# ESP32_main.net
KiCad netlist of a schematic drawn in Altium Designer
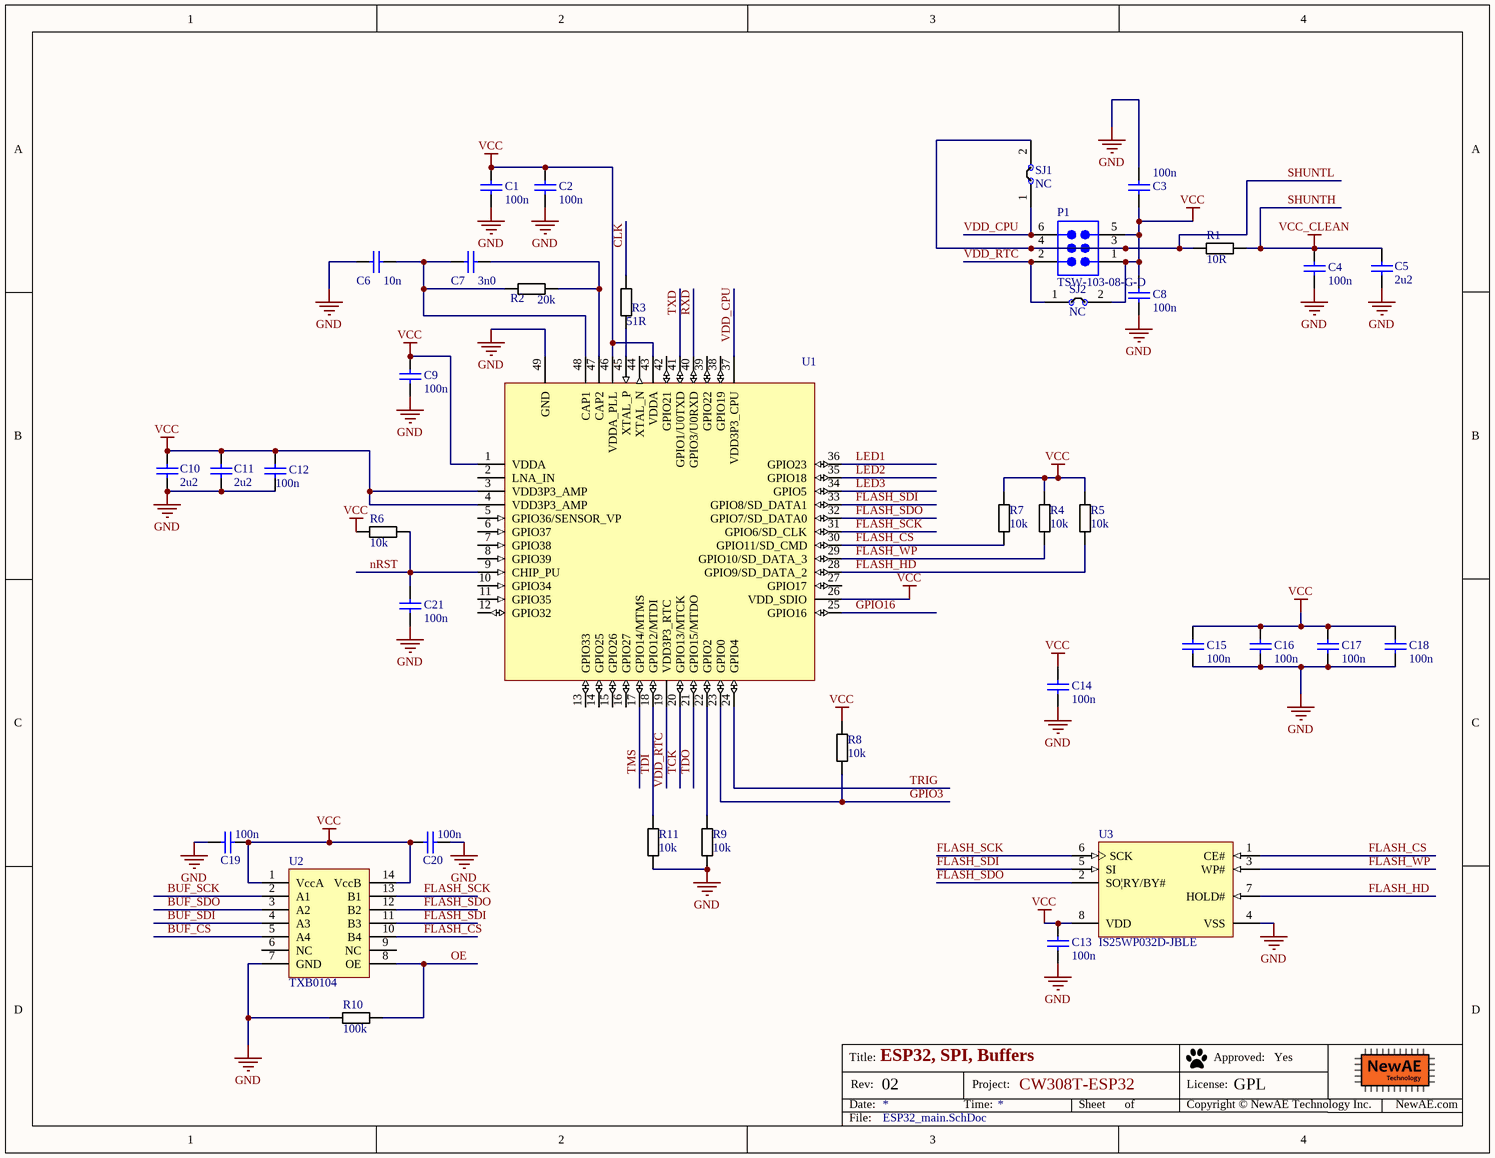
[diagram p0: ESP32_main.SchDoc]

(export (version "E")
  (design (tool "Eeschema 10.0.6"))
  (components
    (comp (ref "C1")
      (value "100n")
      (footprint "CAPC0603_M")
      (description "100n, 0603")
      (fields (field (name "PART NUMBER") "CCHIP-100n-0603"))
      (libsource (lib "NewAE_AltiumLib") (part "CAP"))
    )
    (comp (ref "C2")
      (value "100n")
      (footprint "CAPC0603_M")
      (description "100n, 0603")
      (fields (field (name "PART NUMBER") "CCHIP-100n-0603"))
      (libsource (lib "NewAE_AltiumLib") (part "CAP"))
    )
    (comp (ref "C3")
      (value "100n")
      (footprint "CAPC0603_M")
      (description "100n, 0603")
      (fields (field (name "PART NUMBER") "CCHIP-100n-0603"))
      (libsource (lib "NewAE_AltiumLib") (part "CAP"))
    )
    (comp (ref "C4")
      (value "100n")
      (footprint "CAPC0603_M")
      (description "100n, 0603")
      (fields (field (name "PART NUMBER") "CCHIP-100n-0603"))
      (libsource (lib "NewAE_AltiumLib") (part "CAP"))
    )
    (comp (ref "C5")
      (value "2u2")
      (footprint "CAPC0603_M")
      (description "2u2, 0603")
      (fields (field (name "PART NUMBER") "CCHIP-2u2-0603"))
      (libsource (lib "NewAE_AltiumLib") (part "CAP"))
    )
    (comp (ref "C6")
      (value "10n")
      (footprint "CAPC0603_M")
      (description "10n, 0603")
      (fields (field (name "PART NUMBER") "CCHIP-10n-0603"))
      (libsource (lib "NewAE_AltiumLib") (part "CAP"))
    )
    (comp (ref "C7")
      (value "3n0")
      (footprint "CAPC0603_M")
      (description "3n0, 0603")
      (fields (field (name "PART NUMBER") "CCHIP-3n0-0603"))
      (libsource (lib "NewAE_AltiumLib") (part "CAP"))
    )
    (comp (ref "C8")
      (value "100n")
      (footprint "CAPC0603_M")
      (description "100n, 0603")
      (fields (field (name "PART NUMBER") "CCHIP-100n-0603"))
      (libsource (lib "NewAE_AltiumLib") (part "CAP"))
    )
    (comp (ref "C9")
      (value "100n")
      (footprint "CAPC0603_M")
      (description "100n, 0603")
      (fields (field (name "PART NUMBER") "CCHIP-100n-0603"))
      (libsource (lib "NewAE_AltiumLib") (part "CAP"))
    )
    (comp (ref "C10")
      (value "2u2")
      (footprint "CAPC0603_M")
      (description "2u2, 0603")
      (fields (field (name "PART NUMBER") "CCHIP-2u2-0603"))
      (libsource (lib "NewAE_AltiumLib") (part "CAP"))
    )
    (comp (ref "C11")
      (value "2u2")
      (footprint "CAPC0603_M")
      (description "2u2, 0603")
      (fields (field (name "PART NUMBER") "CCHIP-2u2-0603"))
      (libsource (lib "NewAE_AltiumLib") (part "CAP"))
    )
    (comp (ref "C12")
      (value "100n")
      (footprint "CAPC0603_M")
      (description "100n, 0603")
      (fields (field (name "PART NUMBER") "CCHIP-100n-0603"))
      (libsource (lib "NewAE_AltiumLib") (part "CAP"))
    )
    (comp (ref "C13")
      (value "100n")
      (footprint "CAPC0603_M")
      (description "100n, 0603")
      (fields (field (name "PART NUMBER") "CCHIP-100n-0603"))
      (libsource (lib "NewAE_AltiumLib") (part "CAP"))
    )
    (comp (ref "C14")
      (value "100n")
      (footprint "CAPC0603_M")
      (description "100n, 0603")
      (fields (field (name "PART NUMBER") "CCHIP-100n-0603"))
      (libsource (lib "NewAE_AltiumLib") (part "CAP"))
    )
    (comp (ref "C15")
      (value "100n")
      (footprint "CAPC0603_M")
      (description "100n, 0603")
      (fields (field (name "PART NUMBER") "CCHIP-100n-0603"))
      (libsource (lib "NewAE_AltiumLib") (part "CAP"))
    )
    (comp (ref "C16")
      (value "100n")
      (footprint "CAPC0603_M")
      (description "100n, 0603")
      (fields (field (name "PART NUMBER") "CCHIP-100n-0603"))
      (libsource (lib "NewAE_AltiumLib") (part "CAP"))
    )
    (comp (ref "C17")
      (value "100n")
      (footprint "CAPC0603_M")
      (description "100n, 0603")
      (fields (field (name "PART NUMBER") "CCHIP-100n-0603"))
      (libsource (lib "NewAE_AltiumLib") (part "CAP"))
    )
    (comp (ref "C18")
      (value "100n")
      (footprint "CAPC0603_M")
      (description "100n, 0603")
      (fields (field (name "PART NUMBER") "CCHIP-100n-0603"))
      (libsource (lib "NewAE_AltiumLib") (part "CAP"))
    )
    (comp (ref "C19")
      (value "100n")
      (footprint "CAPC0603_M")
      (description "100n, 0603")
      (fields (field (name "PART NUMBER") "CCHIP-100n-0603"))
      (libsource (lib "NewAE_AltiumLib") (part "CAP"))
    )
    (comp (ref "C20")
      (value "100n")
      (footprint "CAPC0603_M")
      (description "100n, 0603")
      (fields (field (name "PART NUMBER") "CCHIP-100n-0603"))
      (libsource (lib "NewAE_AltiumLib") (part "CAP"))
    )
    (comp (ref "C21")
      (value "100n")
      (footprint "CAPC0603_M")
      (description "100n, 0603")
      (fields (field (name "PART NUMBER") "CCHIP-100n-0603"))
      (libsource (lib "NewAE_AltiumLib") (part "CAP"))
    )
    (comp (ref "P1")
      (value "TSW-103-08-G-D")
      (footprint "SMTC-TSW-103-08-X-D")
      (fields (field (name "MANUFACTURER") "Samtec"))
      (libsource (lib "Altium Content Vault") (part "SMTC-TSW-103-08-X-D"))
    )
    (comp (ref "R1")
      (value "10R")
      (footprint "RESC1608X55N")
      (description "10R res, 0603, 1%, 1/10W")
      (fields (field (name "PART NUMBER") "RCHIP-10R-0603") (field (name "TOLERANCE") "1%"))
      (libsource (lib "NewAE_AltiumLib") (part "RES-EU"))
    )
    (comp (ref "R2")
      (value "20k")
      (footprint "RESC1608X55N")
      (description "20k res, 0603, 1%, 1/10W")
      (fields (field (name "PART NUMBER") "RCHIP-20K-0603") (field (name "TOLERANCE") "1%"))
      (libsource (lib "NewAE_AltiumLib") (part "RES-EU"))
    )
    (comp (ref "R3")
      (value "51R")
      (footprint "RESC1608X55N")
      (description "51R res, 0603, 1%, 1/10W")
      (fields (field (name "PART NUMBER") "RCHIP-51R-0603") (field (name "TOLERANCE") "1%"))
      (libsource (lib "") (part "RES-EU_1"))
    )
    (comp (ref "R4")
      (value "10k")
      (footprint "RESC1608X55N")
      (description "10k res, 0603, 1%, 1/10W")
      (fields (field (name "PART NUMBER") "RCHIP-10K-0603") (field (name "TOLERANCE") "1%"))
      (libsource (lib "") (part "RES-EU_1"))
    )
    (comp (ref "R5")
      (value "10k")
      (footprint "RESC1608X55N")
      (description "10k res, 0603, 1%, 1/10W")
      (fields (field (name "PART NUMBER") "RCHIP-10K-0603") (field (name "TOLERANCE") "1%"))
      (libsource (lib "") (part "RES-EU_1"))
    )
    (comp (ref "R6")
      (value "10k")
      (footprint "RESC1608X55N")
      (description "10k res, 0603, 1%, 1/10W")
      (fields (field (name "PART NUMBER") "RCHIP-10K-0603") (field (name "TOLERANCE") "1%"))
      (libsource (lib "NewAE_AltiumLib") (part "RES-EU"))
    )
    (comp (ref "R7")
      (value "10k")
      (footprint "RESC1608X55N")
      (description "10k res, 0603, 1%, 1/10W")
      (fields (field (name "PART NUMBER") "RCHIP-10K-0603") (field (name "TOLERANCE") "1%"))
      (libsource (lib "") (part "RES-EU_1"))
    )
    (comp (ref "R8")
      (value "10k")
      (footprint "RESC1608X55N")
      (description "10k res, 0603, 1%, 1/10W")
      (fields (field (name "PART NUMBER") "RCHIP-10K-0603") (field (name "TOLERANCE") "1%"))
      (libsource (lib "") (part "RES-EU_1"))
    )
    (comp (ref "R9")
      (value "10k")
      (footprint "RESC1608X55N")
      (description "10k res, 0603, 1%, 1/10W")
      (fields (field (name "PART NUMBER") "RCHIP-10K-0603") (field (name "TOLERANCE") "1%"))
      (libsource (lib "") (part "RES-EU_1"))
    )
    (comp (ref "R10")
      (value "100k")
      (footprint "RESC1608X55N")
      (description "100k res, 0603, 1%, 1/10W")
      (fields (field (name "PART NUMBER") "RCHIP-100K-0603") (field (name "TOLERANCE") "1%"))
      (libsource (lib "NewAE_AltiumLib") (part "RES-EU"))
    )
    (comp (ref "R11")
      (value "10k")
      (footprint "RESC1608X55N")
      (description "10k res, 0603, 1%, 1/10W")
      (fields (field (name "PART NUMBER") "RCHIP-10K-0603") (field (name "TOLERANCE") "1%"))
      (libsource (lib "") (part "RES-EU_1"))
    )
    (comp (ref "SJ1")
      (value "NC")
      (footprint "SJ_2S_NC")
      (description "Solder Jumper, NC")
      (fields (field (name "PART NUMBER") "SJ_2S"))
      (libsource (lib "NewAE_AltiumLib") (part "SJ_2S"))
    )
    (comp (ref "SJ2")
      (value "NC")
      (footprint "SJ_2S_NC")
      (description "Solder Jumper, NC")
      (fields (field (name "PART NUMBER") "SJ_2S"))
      (libsource (lib "NewAE_AltiumLib") (part "SJ_2S"))
    )
    (comp (ref "U1")
      (value "ESP32")
      (footprint "QFN48_6x6_0.4mm")
      (description "Dual-Core WiFi/Bluetooth Chip")
      (libsource (lib "NewAE_AltiumLib") (part "ESP32"))
    )
    (comp (ref "U2")
      (value "TXB0104")
      (footprint "SOIC14 (R-PDSO-G14)")
      (description "IC 4BIT NON-INV TRANSLTR 14-SOIC")
      (fields (field (name "PART NUMBER") "TXB0104DR"))
      (libsource (lib "NewAE_AltiumLib") (part "TXS104"))
    )
    (comp (ref "U3")
      (value "IS25WP032D-JBLE")
      (footprint "SOIC8_WIDE_NARROW")
      (description "32MB QPI/QPI/QSPI 8-PIN SOP 208M")
      (libsource (lib "NewAE_AltiumLib") (part "MCHP-SST25VFXXXB-SOIX-8"))
    )
  )
  (nets
    (net (code "1") (name "/BUF_CS") (class "Default")
      (node (ref "U2") (pin "5") (pinfunction "A4_5") (pintype "passive"))
    )
    (net (code "2") (name "/BUF_SCK") (class "Default")
      (node (ref "U2") (pin "2") (pinfunction "A1_2") (pintype "passive"))
    )
    (net (code "3") (name "/BUF_SDI") (class "Default")
      (node (ref "U2") (pin "4") (pinfunction "A3_4") (pintype "passive"))
    )
    (net (code "4") (name "/BUF_SDO") (class "Default")
      (node (ref "U2") (pin "3") (pinfunction "A2_3") (pintype "passive"))
    )
    (net (code "5") (name "/CLK") (class "Default")
      (node (ref "R3") (pin "1") (pinfunction "1_1") (pintype "passive"))
    )
    (net (code "6") (name "/FLASH_CS") (class "Default")
      (node (ref "R7") (pin "2") (pinfunction "2_2") (pintype "passive"))
      (node (ref "U1") (pin "30") (pinfunction "GPIO11/SD_CMD_30") (pintype "bidirectional"))
      (node (ref "U2") (pin "10") (pinfunction "B4_10") (pintype "passive"))
      (node (ref "U3") (pin "1") (pinfunction "CE#_1") (pintype "input"))
    )
    (net (code "7") (name "/FLASH_HD") (class "Default")
      (node (ref "R5") (pin "2") (pinfunction "2_2") (pintype "passive"))
      (node (ref "U1") (pin "28") (pinfunction "GPIO9/SD_DATA_2_28") (pintype "bidirectional"))
      (node (ref "U3") (pin "7") (pinfunction "HOLD#_7") (pintype "input"))
    )
    (net (code "8") (name "/FLASH_SCK") (class "Default")
      (node (ref "U1") (pin "31") (pinfunction "GPIO6/SD_CLK_31") (pintype "bidirectional"))
      (node (ref "U2") (pin "13") (pinfunction "B1_13") (pintype "passive"))
      (node (ref "U3") (pin "6") (pinfunction "SCK_6") (pintype "input"))
    )
    (net (code "9") (name "/FLASH_SDI") (class "Default")
      (node (ref "U1") (pin "33") (pinfunction "GPIO8/SD_DATA1_33") (pintype "bidirectional"))
      (node (ref "U2") (pin "11") (pinfunction "B3_11") (pintype "passive"))
      (node (ref "U3") (pin "5") (pinfunction "SI_5") (pintype "input"))
    )
    (net (code "10") (name "/FLASH_SDO") (class "Default")
      (node (ref "U1") (pin "32") (pinfunction "GPIO7/SD_DATA0_32") (pintype "bidirectional"))
      (node (ref "U2") (pin "12") (pinfunction "B2_12") (pintype "passive"))
      (node (ref "U3") (pin "2") (pinfunction "SO¦RY/BY#_2") (pintype "tri_state"))
    )
    (net (code "11") (name "/FLASH_WP") (class "Default")
      (node (ref "R4") (pin "2") (pinfunction "2_2") (pintype "passive"))
      (node (ref "U1") (pin "29") (pinfunction "GPIO10/SD_DATA_3_29") (pintype "bidirectional"))
      (node (ref "U3") (pin "3") (pinfunction "WP#_3") (pintype "input"))
    )
    (net (code "12") (name "/GPIO3") (class "Default")
      (node (ref "R8") (pin "2") (pinfunction "2_2") (pintype "passive"))
      (node (ref "U1") (pin "23") (pinfunction "GPIO0_23") (pintype "bidirectional"))
    )
    (net (code "13") (name "/GPIO16") (class "Default")
      (node (ref "U1") (pin "25") (pinfunction "GPIO16_25") (pintype "bidirectional"))
    )
    (net (code "14") (name "/LED1") (class "Default")
      (node (ref "U1") (pin "36") (pinfunction "GPIO23_36") (pintype "bidirectional"))
    )
    (net (code "15") (name "/LED2") (class "Default")
      (node (ref "U1") (pin "35") (pinfunction "GPIO18_35") (pintype "bidirectional"))
    )
    (net (code "16") (name "/LED3") (class "Default")
      (node (ref "U1") (pin "34") (pinfunction "GPIO5_34") (pintype "bidirectional"))
    )
    (net (code "17") (name "/OE") (class "Default")
      (node (ref "R10") (pin "2") (pinfunction "2_2") (pintype "passive"))
      (node (ref "U2") (pin "8") (pinfunction "OE_8") (pintype "passive"))
    )
    (net (code "18") (name "/RXD") (class "Default")
      (node (ref "U1") (pin "40") (pinfunction "GPIO3/U0RXD_40") (pintype "bidirectional"))
    )
    (net (code "19") (name "/SHUNTL") (class "Default")
      (node (ref "P1") (pin "3") (pinfunction "3_3") (pintype "passive"))
      (node (ref "P1") (pin "4") (pinfunction "4_4") (pintype "passive"))
      (node (ref "R1") (pin "1") (pinfunction "1_1") (pintype "passive"))
      (node (ref "SJ1") (pin "2") (pinfunction "2_2") (pintype "passive"))
    )
    (net (code "20") (name "/TCK") (class "Default")
      (node (ref "U1") (pin "20") (pinfunction "GPIO13/MTCK_20") (pintype "bidirectional"))
    )
    (net (code "21") (name "/TDI") (class "Default")
      (node (ref "R11") (pin "1") (pinfunction "1_1") (pintype "passive"))
      (node (ref "U1") (pin "18") (pinfunction "GPIO12/MTDI_18") (pintype "bidirectional"))
    )
    (net (code "22") (name "/TDO") (class "Default")
      (node (ref "U1") (pin "21") (pinfunction "GPIO15/MTDO_21") (pintype "bidirectional"))
    )
    (net (code "23") (name "/TMS") (class "Default")
      (node (ref "U1") (pin "17") (pinfunction "GPIO14/MTMS_17") (pintype "bidirectional"))
    )
    (net (code "24") (name "/TRIG") (class "Default")
      (node (ref "U1") (pin "24") (pinfunction "GPIO4_24") (pintype "bidirectional"))
    )
    (net (code "25") (name "/TXD") (class "Default")
      (node (ref "U1") (pin "41") (pinfunction "GPIO1/U0TXD_41") (pintype "bidirectional"))
    )
    (net (code "26") (name "/VDD_CPU") (class "Default")
      (node (ref "P1") (pin "6") (pinfunction "6_6") (pintype "passive"))
      (node (ref "SJ1") (pin "1") (pinfunction "1_1") (pintype "passive"))
      (node (ref "U1") (pin "37") (pinfunction "VDD3P3_CPU_37") (pintype "power_in"))
    )
    (net (code "27") (name "/VDD_RTC") (class "Default")
      (node (ref "P1") (pin "2") (pinfunction "2_2") (pintype "passive"))
      (node (ref "SJ2") (pin "1") (pinfunction "1_1") (pintype "passive"))
      (node (ref "U1") (pin "19") (pinfunction "VDD3P3_RTC_19") (pintype "power_in"))
    )
    (net (code "28") (name "/nRST") (class "Default")
      (node (ref "C21") (pin "1") (pinfunction "1_1") (pintype "passive"))
      (node (ref "R6") (pin "2") (pinfunction "2_2") (pintype "passive"))
      (node (ref "U1") (pin "9") (pinfunction "CHIP_PU_9") (pintype "input"))
    )
    (net (code "29") (name "GND") (class "Default")
      (node (ref "C1") (pin "2") (pinfunction "2_2") (pintype "passive"))
      (node (ref "C10") (pin "2") (pinfunction "2_2") (pintype "passive"))
      (node (ref "C11") (pin "2") (pinfunction "2_2") (pintype "passive"))
      (node (ref "C12") (pin "2") (pinfunction "2_2") (pintype "passive"))
      (node (ref "C13") (pin "2") (pinfunction "2_2") (pintype "passive"))
      (node (ref "C14") (pin "2") (pinfunction "2_2") (pintype "passive"))
      (node (ref "C15") (pin "2") (pinfunction "2_2") (pintype "passive"))
      (node (ref "C16") (pin "2") (pinfunction "2_2") (pintype "passive"))
      (node (ref "C17") (pin "2") (pinfunction "2_2") (pintype "passive"))
      (node (ref "C18") (pin "2") (pinfunction "2_2") (pintype "passive"))
      (node (ref "C19") (pin "1") (pinfunction "1_1") (pintype "passive"))
      (node (ref "C2") (pin "2") (pinfunction "2_2") (pintype "passive"))
      (node (ref "C20") (pin "2") (pinfunction "2_2") (pintype "passive"))
      (node (ref "C21") (pin "2") (pinfunction "2_2") (pintype "passive"))
      (node (ref "C3") (pin "1") (pinfunction "1_1") (pintype "passive"))
      (node (ref "C4") (pin "2") (pinfunction "2_2") (pintype "passive"))
      (node (ref "C5") (pin "2") (pinfunction "2_2") (pintype "passive"))
      (node (ref "C6") (pin "1") (pinfunction "1_1") (pintype "passive"))
      (node (ref "C8") (pin "2") (pinfunction "2_2") (pintype "passive"))
      (node (ref "C9") (pin "2") (pinfunction "2_2") (pintype "passive"))
      (node (ref "R10") (pin "1") (pinfunction "1_1") (pintype "passive"))
      (node (ref "R11") (pin "2") (pinfunction "2_2") (pintype "passive"))
      (node (ref "R9") (pin "2") (pinfunction "2_2") (pintype "passive"))
      (node (ref "U1") (pin "49") (pinfunction "GND_49") (pintype "passive"))
      (node (ref "U2") (pin "7") (pinfunction "GND_7") (pintype "passive"))
      (node (ref "U3") (pin "4") (pinfunction "VSS_4") (pintype "power_in"))
    )
    (net (code "30") (name "Net-(U1-CAP1)") (class "Default")
      (node (ref "C6") (pin "2") (pinfunction "2_2") (pintype "passive"))
      (node (ref "C7") (pin "1") (pinfunction "1_1") (pintype "passive"))
      (node (ref "R2") (pin "1") (pinfunction "1_1") (pintype "passive"))
      (node (ref "U1") (pin "48") (pinfunction "CAP1_48") (pintype "passive"))
    )
    (net (code "31") (name "Net-(U1-CAP2)") (class "Default")
      (node (ref "C7") (pin "2") (pinfunction "2_2") (pintype "passive"))
      (node (ref "R2") (pin "2") (pinfunction "2_2") (pintype "passive"))
      (node (ref "U1") (pin "47") (pinfunction "CAP2_47") (pintype "passive"))
    )
    (net (code "32") (name "Net-(U1-GPIO2)") (class "Default")
      (node (ref "R9") (pin "1") (pinfunction "1_1") (pintype "passive"))
      (node (ref "U1") (pin "22") (pinfunction "GPIO2_22") (pintype "bidirectional"))
    )
    (net (code "33") (name "Net-(U1-XTAL_P)") (class "Default")
      (node (ref "R3") (pin "2") (pinfunction "2_2") (pintype "passive"))
      (node (ref "U1") (pin "45") (pinfunction "XTAL_P_45") (pintype "input"))
    )
    (net (code "34") (name "VCC") (class "Default")
      (node (ref "C1") (pin "1") (pinfunction "1_1") (pintype "passive"))
      (node (ref "C10") (pin "1") (pinfunction "1_1") (pintype "passive"))
      (node (ref "C11") (pin "1") (pinfunction "1_1") (pintype "passive"))
      (node (ref "C12") (pin "1") (pinfunction "1_1") (pintype "passive"))
      (node (ref "C13") (pin "1") (pinfunction "1_1") (pintype "passive"))
      (node (ref "C14") (pin "1") (pinfunction "1_1") (pintype "passive"))
      (node (ref "C15") (pin "1") (pinfunction "1_1") (pintype "passive"))
      (node (ref "C16") (pin "1") (pinfunction "1_1") (pintype "passive"))
      (node (ref "C17") (pin "1") (pinfunction "1_1") (pintype "passive"))
      (node (ref "C18") (pin "1") (pinfunction "1_1") (pintype "passive"))
      (node (ref "C19") (pin "2") (pinfunction "2_2") (pintype "passive"))
      (node (ref "C2") (pin "1") (pinfunction "1_1") (pintype "passive"))
      (node (ref "C20") (pin "1") (pinfunction "1_1") (pintype "passive"))
      (node (ref "C3") (pin "2") (pinfunction "2_2") (pintype "passive"))
      (node (ref "C8") (pin "1") (pinfunction "1_1") (pintype "passive"))
      (node (ref "C9") (pin "1") (pinfunction "1_1") (pintype "passive"))
      (node (ref "P1") (pin "1") (pinfunction "1_1") (pintype "passive"))
      (node (ref "P1") (pin "5") (pinfunction "5_5") (pintype "passive"))
      (node (ref "R4") (pin "1") (pinfunction "1_1") (pintype "passive"))
      (node (ref "R5") (pin "1") (pinfunction "1_1") (pintype "passive"))
      (node (ref "R6") (pin "1") (pinfunction "1_1") (pintype "passive"))
      (node (ref "R7") (pin "1") (pinfunction "1_1") (pintype "passive"))
      (node (ref "R8") (pin "1") (pinfunction "1_1") (pintype "passive"))
      (node (ref "SJ2") (pin "2") (pinfunction "2_2") (pintype "passive"))
      (node (ref "U1") (pin "1") (pinfunction "VDDA_1") (pintype "power_in"))
      (node (ref "U1") (pin "26") (pinfunction "VDD_SDIO_26") (pintype "power_in"))
      (node (ref "U1") (pin "3") (pinfunction "VDD3P3_AMP_3") (pintype "power_in"))
      (node (ref "U1") (pin "4") (pinfunction "VDD3P3_AMP_4") (pintype "power_in"))
      (node (ref "U1") (pin "43") (pinfunction "VDDA_43") (pintype "power_in"))
      (node (ref "U1") (pin "46") (pinfunction "VDDA_PLL_46") (pintype "power_in"))
      (node (ref "U2") (pin "1") (pinfunction "VccA_1") (pintype "passive"))
      (node (ref "U2") (pin "14") (pinfunction "VccB_14") (pintype "passive"))
      (node (ref "U3") (pin "8") (pinfunction "VDD_8") (pintype "power_in"))
    )
    (net (code "35") (name "VCC_CLEAN") (class "Default")
      (node (ref "C4") (pin "1") (pinfunction "1_1") (pintype "passive"))
      (node (ref "C5") (pin "1") (pinfunction "1_1") (pintype "passive"))
      (node (ref "R1") (pin "2") (pinfunction "2_2") (pintype "passive"))
    )
    (net (code "36") (name "unconnected-(U1-GPIO17-Pad27)") (class "Default")
      (node (ref "U1") (pin "27") (pinfunction "GPIO17_27") (pintype "bidirectional"))
    )
    (net (code "37") (name "unconnected-(U1-GPIO19-Pad38)") (class "Default")
      (node (ref "U1") (pin "38") (pinfunction "GPIO19_38") (pintype "bidirectional"))
    )
    (net (code "38") (name "unconnected-(U1-GPIO21-Pad42)") (class "Default")
      (node (ref "U1") (pin "42") (pinfunction "GPIO21_42") (pintype "bidirectional"))
    )
    (net (code "39") (name "unconnected-(U1-GPIO22-Pad39)") (class "Default")
      (node (ref "U1") (pin "39") (pinfunction "GPIO22_39") (pintype "bidirectional"))
    )
    (net (code "40") (name "unconnected-(U1-GPIO25-Pad14)") (class "Default")
      (node (ref "U1") (pin "14") (pinfunction "GPIO25_14") (pintype "bidirectional"))
    )
    (net (code "41") (name "unconnected-(U1-GPIO26-Pad15)") (class "Default")
      (node (ref "U1") (pin "15") (pinfunction "GPIO26_15") (pintype "bidirectional"))
    )
    (net (code "42") (name "unconnected-(U1-GPIO27-Pad16)") (class "Default")
      (node (ref "U1") (pin "16") (pinfunction "GPIO27_16") (pintype "bidirectional"))
    )
    (net (code "43") (name "unconnected-(U1-GPIO32-Pad12)") (class "Default")
      (node (ref "U1") (pin "12") (pinfunction "GPIO32_12") (pintype "bidirectional"))
    )
    (net (code "44") (name "unconnected-(U1-GPIO33-Pad13)") (class "Default")
      (node (ref "U1") (pin "13") (pinfunction "GPIO33_13") (pintype "bidirectional"))
    )
    (net (code "45") (name "unconnected-(U1-GPIO34-Pad10)") (class "Default")
      (node (ref "U1") (pin "10") (pinfunction "GPIO34_10") (pintype "input"))
    )
    (net (code "46") (name "unconnected-(U1-GPIO35-Pad11)") (class "Default")
      (node (ref "U1") (pin "11") (pinfunction "GPIO35_11") (pintype "input"))
    )
    (net (code "47") (name "unconnected-(U1-GPIO36{slash}SENSOR_VP-Pad5)") (class "Default")
      (node (ref "U1") (pin "5") (pinfunction "GPIO36/SENSOR_VP_5") (pintype "input"))
    )
    (net (code "48") (name "unconnected-(U1-GPIO37-Pad6)") (class "Default")
      (node (ref "U1") (pin "6") (pinfunction "GPIO37_6") (pintype "input"))
    )
    (net (code "49") (name "unconnected-(U1-GPIO38-Pad7)") (class "Default")
      (node (ref "U1") (pin "7") (pinfunction "GPIO38_7") (pintype "input"))
    )
    (net (code "50") (name "unconnected-(U1-GPIO39-Pad8)") (class "Default")
      (node (ref "U1") (pin "8") (pinfunction "GPIO39_8") (pintype "input"))
    )
    (net (code "51") (name "unconnected-(U1-LNA_IN-Pad2)") (class "Default")
      (node (ref "U1") (pin "2") (pinfunction "LNA_IN_2") (pintype "passive"))
    )
    (net (code "52") (name "unconnected-(U1-XTAL_N-Pad44)") (class "Default")
      (node (ref "U1") (pin "44") (pinfunction "XTAL_N_44") (pintype "output"))
    )
    (net (code "53") (name "unconnected-(U2-NC-Pad6)") (class "Default")
      (node (ref "U2") (pin "6") (pinfunction "NC_6") (pintype "passive"))
    )
    (net (code "54") (name "unconnected-(U2-NC-Pad9)") (class "Default")
      (node (ref "U2") (pin "9") (pinfunction "NC_9") (pintype "passive"))
    )
  )
)
